# breaking_bitcoin.net
KiCad netlist of a schematic drawn in EAGLE
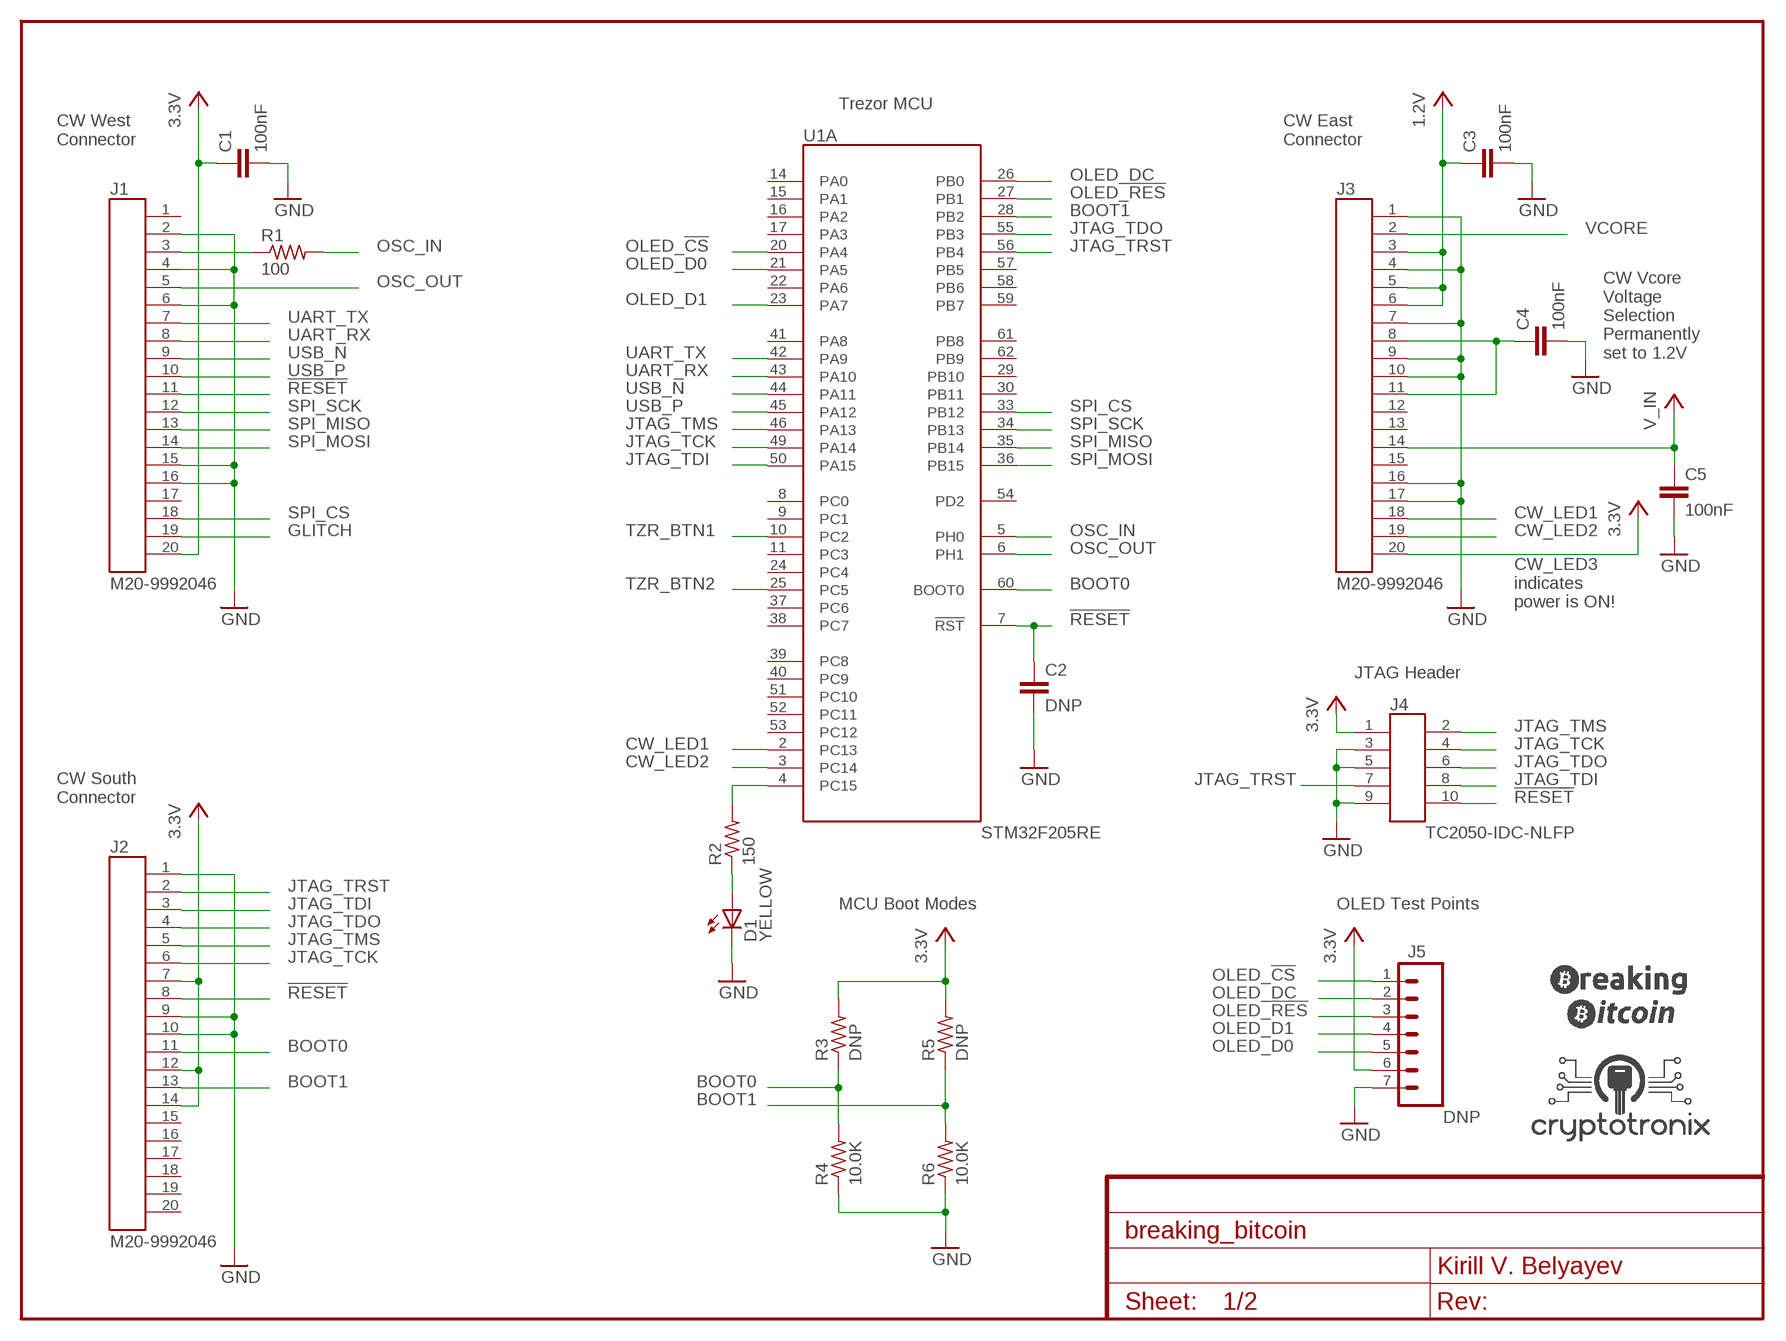
[diagram p0: schematic, sheet 1]
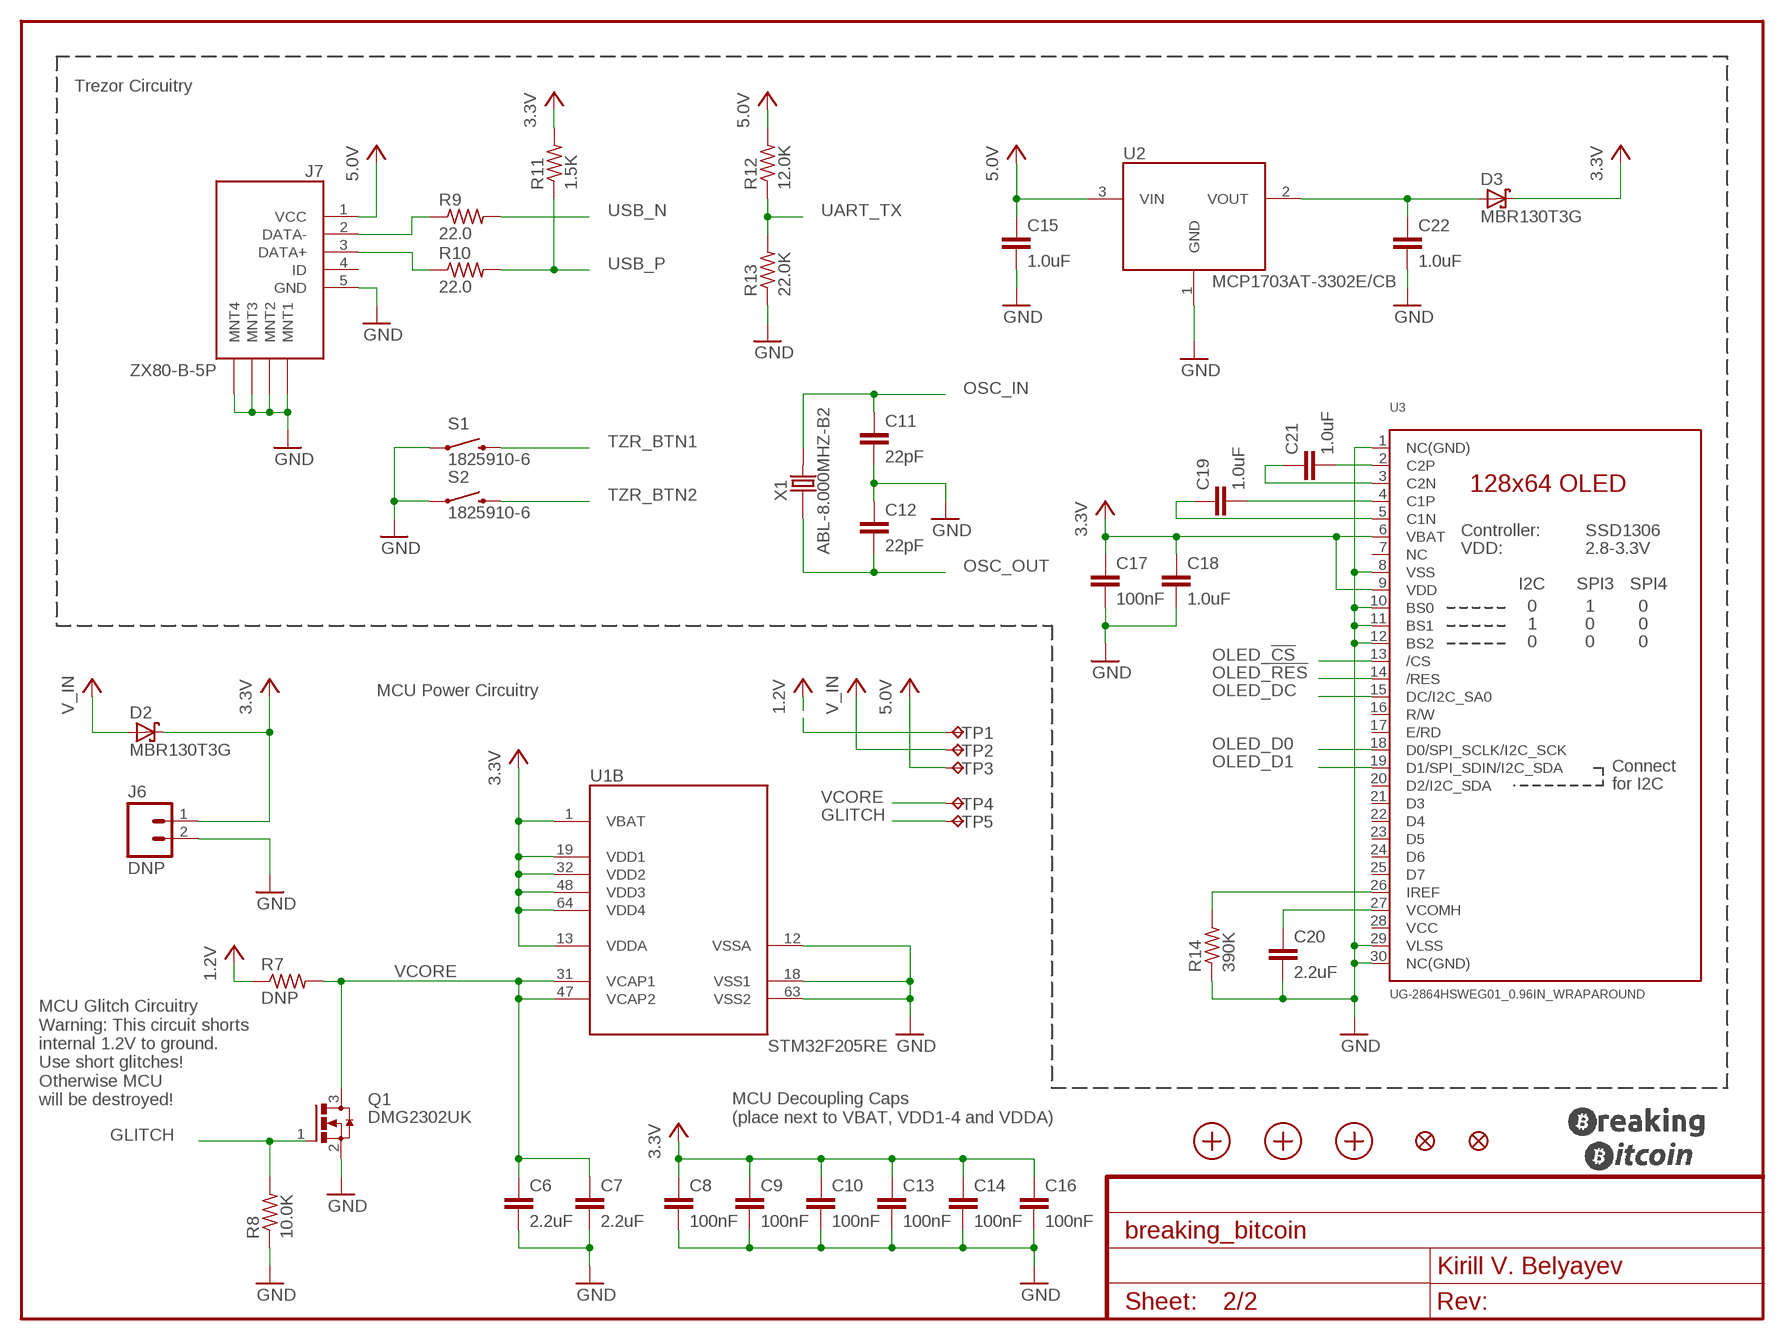
[diagram p1: schematic, sheet 2]

(export (version "E")
  (design (tool "Eeschema 10.0.6"))
  (components
    (comp (ref "C6")
      (value "2.2uF")
      (footprint "eagle-import:C0603")
      (libsource (lib "eagle-import") (part "C-EUC0603"))
    )
    (comp (ref "C7")
      (value "2.2uF")
      (footprint "eagle-import:C0603")
      (libsource (lib "eagle-import") (part "C-EUC0603"))
    )
    (comp (ref "C8")
      (value "100nF")
      (footprint "eagle-import:C0603")
      (libsource (lib "eagle-import") (part "C-EUC0603"))
    )
    (comp (ref "C9")
      (value "100nF")
      (footprint "eagle-import:C0603")
      (libsource (lib "eagle-import") (part "C-EUC0603"))
    )
    (comp (ref "C10")
      (value "100nF")
      (footprint "eagle-import:C0603")
      (libsource (lib "eagle-import") (part "C-EUC0603"))
    )
    (comp (ref "C11")
      (value "22pF")
      (footprint "eagle-import:C0603")
      (libsource (lib "eagle-import") (part "C-EUC0603"))
    )
    (comp (ref "C12")
      (value "22pF")
      (footprint "eagle-import:C0603")
      (libsource (lib "eagle-import") (part "C-EUC0603"))
    )
    (comp (ref "C13")
      (value "100nF")
      (footprint "eagle-import:C0603")
      (libsource (lib "eagle-import") (part "C-EUC0603"))
    )
    (comp (ref "C14")
      (value "100nF")
      (footprint "eagle-import:C0603")
      (libsource (lib "eagle-import") (part "C-EUC0603"))
    )
    (comp (ref "C15")
      (value "1.0uF")
      (footprint "eagle-import:C0603")
      (libsource (lib "eagle-import") (part "C-EUC0603"))
    )
    (comp (ref "C16")
      (value "100nF")
      (footprint "eagle-import:C0603")
      (libsource (lib "eagle-import") (part "C-EUC0603"))
    )
    (comp (ref "C17")
      (value "100nF")
      (footprint "eagle-import:C0603")
      (libsource (lib "eagle-import") (part "C-EUC0603"))
    )
    (comp (ref "C18")
      (value "1.0uF")
      (footprint "eagle-import:C0603")
      (libsource (lib "eagle-import") (part "C-EUC0603"))
    )
    (comp (ref "C19")
      (value "1.0uF")
      (footprint "eagle-import:C0603")
      (libsource (lib "eagle-import") (part "C-EUC0603"))
    )
    (comp (ref "C20")
      (value "2.2uF")
      (footprint "eagle-import:C0603")
      (libsource (lib "eagle-import") (part "C-EUC0603"))
    )
    (comp (ref "C21")
      (value "1.0uF")
      (footprint "eagle-import:C0603")
      (libsource (lib "eagle-import") (part "C-EUC0603"))
    )
    (comp (ref "C22")
      (value "1.0uF")
      (footprint "eagle-import:C0603")
      (libsource (lib "eagle-import") (part "C-EUC0603"))
    )
    (comp (ref "D2")
      (value "MBR130T3G")
      (footprint "eagle-import:SOD123")
      (fields (field (name "MANUFACTURER") "ON Semiconductor"))
      (libsource (lib "eagle-import") (part "MBR130T3G"))
    )
    (comp (ref "D3")
      (value "MBR130T3G")
      (footprint "eagle-import:SOD123")
      (fields (field (name "MANUFACTURER") "ON Semiconductor"))
      (libsource (lib "eagle-import") (part "MBR130T3G"))
    )
    (comp (ref "FD1")
      (value "FIDUCIALUFIDUCIAL")
      (footprint "eagle-import:MICRO-FIDUCIAL")
      (libsource (lib "eagle-import") (part "FIDUCIALUFIDUCIAL"))
    )
    (comp (ref "FD2")
      (value "FIDUCIALUFIDUCIAL")
      (footprint "eagle-import:MICRO-FIDUCIAL")
      (libsource (lib "eagle-import") (part "FIDUCIALUFIDUCIAL"))
    )
    (comp (ref "J6")
      (value "DNP")
      (footprint "eagle-import:M20-9990246")
      (fields (field (name "MAN-PART_NUM") "M20-9990246") (field (name "MANUFACTURER") "Harwin Inc."))
      (libsource (lib "eagle-import") (part "M20-9990246"))
    )
    (comp (ref "J7")
      (value "ZX80-B-5P")
      (footprint "eagle-import:ZX80-B-5P")
      (fields (field (name "MAN-PART_NUM") "ZX80-B-5P(30)") (field (name "MANUFACTURER") "Hirose"))
      (libsource (lib "eagle-import") (part "ZX80-B-5P"))
    )
    (comp (ref "MNT1")
      (value "MOUNT-HOLE-NO-PLATE4-40")
      (footprint "eagle-import:MOUNT-HOLE-NO-PLATE-4-40")
      (libsource (lib "eagle-import") (part "MOUNT-HOLE-NO-PLATE4-40"))
    )
    (comp (ref "MNT2")
      (value "MOUNT-HOLE-NO-PLATE4-40")
      (footprint "eagle-import:MOUNT-HOLE-NO-PLATE-4-40")
      (libsource (lib "eagle-import") (part "MOUNT-HOLE-NO-PLATE4-40"))
    )
    (comp (ref "MNT3")
      (value "MOUNT-HOLE-NO-PLATE4-40")
      (footprint "eagle-import:MOUNT-HOLE-NO-PLATE-4-40")
      (libsource (lib "eagle-import") (part "MOUNT-HOLE-NO-PLATE4-40"))
    )
    (comp (ref "Q1")
      (value "DMG2302UK")
      (footprint "eagle-import:DMG2302UK")
      (fields (field (name "MANUFACTURER") "Diodes Inc."))
      (libsource (lib "eagle-import") (part "DMG2302UK"))
    )
    (comp (ref "R7")
      (value "DNP")
      (footprint "eagle-import:R0603")
      (libsource (lib "eagle-import") (part "R-US_R0603"))
    )
    (comp (ref "R8")
      (value "10.0K")
      (footprint "eagle-import:R0603")
      (libsource (lib "eagle-import") (part "R-US_R0603"))
    )
    (comp (ref "R9")
      (value "22.0")
      (footprint "eagle-import:R0603")
      (libsource (lib "eagle-import") (part "R-US_R0603"))
    )
    (comp (ref "R10")
      (value "22.0")
      (footprint "eagle-import:R0603")
      (libsource (lib "eagle-import") (part "R-US_R0603"))
    )
    (comp (ref "R11")
      (value "1.5K")
      (footprint "eagle-import:R0603")
      (libsource (lib "eagle-import") (part "R-US_R0603"))
    )
    (comp (ref "R12")
      (value "12.0K")
      (footprint "eagle-import:R0603")
      (libsource (lib "eagle-import") (part "R-US_R0603"))
    )
    (comp (ref "R13")
      (value "22.0K")
      (footprint "eagle-import:R0603")
      (libsource (lib "eagle-import") (part "R-US_R0603"))
    )
    (comp (ref "R14")
      (value "390K")
      (footprint "eagle-import:R0603")
      (libsource (lib "eagle-import") (part "R-US_R0603"))
    )
    (comp (ref "S1")
      (value "1825910-6")
      (footprint "eagle-import:SWITCH-TACT-TH")
      (fields
        (field (name "MANUFACTURER") "TE Connectivity")
        (field (name "MAN-PART_NUM") "1825910-6")
        (field (name "MANUFACTURER_1") "TE Connectivity")
      )
      (libsource (lib "eagle-import") (part "SWITCH-TACT-TH"))
    )
    (comp (ref "S2")
      (value "1825910-6")
      (footprint "eagle-import:SWITCH-TACT-TH")
      (fields
        (field (name "MANUFACTURER") "TE Connectivity")
        (field (name "MAN-PART_NUM") "1825910-6")
        (field (name "MANUFACTURER_1") "TE Connectivity")
      )
      (libsource (lib "eagle-import") (part "SWITCH-TACT-TH"))
    )
    (comp (ref "TP1")
      (value "TEST-POINT40MIL")
      (footprint "eagle-import:TEST-POINT-40MILL")
      (libsource (lib "eagle-import") (part "TEST-POINT40MIL"))
    )
    (comp (ref "TP2")
      (value "TEST-POINT40MIL")
      (footprint "eagle-import:TEST-POINT-40MILL")
      (libsource (lib "eagle-import") (part "TEST-POINT40MIL"))
    )
    (comp (ref "TP3")
      (value "TEST-POINT40MIL")
      (footprint "eagle-import:TEST-POINT-40MILL")
      (libsource (lib "eagle-import") (part "TEST-POINT40MIL"))
    )
    (comp (ref "TP4")
      (value "TEST-POINT40MIL")
      (footprint "eagle-import:TEST-POINT-40MILL")
      (libsource (lib "eagle-import") (part "TEST-POINT40MIL"))
    )
    (comp (ref "TP5")
      (value "TEST-POINT40MIL")
      (footprint "eagle-import:TEST-POINT-40MILL")
      (libsource (lib "eagle-import") (part "TEST-POINT40MIL"))
    )
    (comp (ref "U$3")
      (value "BB_LOGO")
      (footprint "eagle-import:BB_LOGO")
      (libsource (lib "eagle-import") (part "BB_LOGO"))
    )
    (comp (ref "U1")
      (value "STM32F205RE")
      (footprint "eagle-import:LQFP64")
      (fields (field (name "MANUFACTURER") "STMicroelectronics"))
      (libsource (lib "eagle-import") (part "STM32F205RE"))
    )
    (comp (ref "U2")
      (value "MCP1703AT-3302E/CB")
      (footprint "eagle-import:MCP1703AT-3302E_CB")
      (fields (field (name "MANUFACTURER") "Microchip Technology"))
      (libsource (lib "eagle-import") (part "MCP1703AT-3302E/CB"))
    )
    (comp (ref "U3")
      (value "UG-2864HSWEG01_0.96IN_WRAPAROUND")
      (footprint "eagle-import:UG-2864HSWEG01_0.96IN_WRAPAROUND")
      (libsource (lib "eagle-import") (part "DISP_OLED_UG-2864HSWEG010.96{dblquote}"))
    )
    (comp (ref "X1")
      (value "ABL-8.000MHZ-B2")
      (footprint "eagle-import:ABL-8.000MHZ-B2")
      (fields (field (name "MANUFACTURER") "Abracon"))
      (libsource (lib "eagle-import") (part "ABL-8.000MHZ-B2"))
    )
    (comp (ref "C1")
      (value "100nF")
      (footprint "eagle-import:C0603")
      (libsource (lib "eagle-import") (part "C-EUC0603"))
    )
    (comp (ref "C2")
      (value "DNP")
      (footprint "eagle-import:C0603")
      (libsource (lib "eagle-import") (part "C-EUC0603"))
    )
    (comp (ref "C3")
      (value "100nF")
      (footprint "eagle-import:C0603")
      (libsource (lib "eagle-import") (part "C-EUC0603"))
    )
    (comp (ref "C4")
      (value "100nF")
      (footprint "eagle-import:C0603")
      (libsource (lib "eagle-import") (part "C-EUC0603"))
    )
    (comp (ref "C5")
      (value "100nF")
      (footprint "eagle-import:C0603")
      (libsource (lib "eagle-import") (part "C-EUC0603"))
    )
    (comp (ref "D1")
      (value "YELLOW")
      (footprint "eagle-import:0603")
      (fields (field (name "MAN-PART_NUM") "LTST-C190") (field (name "MANUFACTURER") "Lite-On Inc."))
      (libsource (lib "eagle-import") (part "LTST-C190YKT"))
    )
    (comp (ref "J1")
      (value "M20-9992046")
      (footprint "eagle-import:M20-9992046")
      (fields (field (name "MANUFACTURER") "Harwin Inc."))
      (libsource (lib "eagle-import") (part "M20-9992046"))
    )
    (comp (ref "J2")
      (value "M20-9992046")
      (footprint "eagle-import:M20-9992046")
      (fields (field (name "MANUFACTURER") "Harwin Inc."))
      (libsource (lib "eagle-import") (part "M20-9992046"))
    )
    (comp (ref "J3")
      (value "M20-9992046")
      (footprint "eagle-import:M20-9992046")
      (fields (field (name "MANUFACTURER") "Harwin Inc."))
      (libsource (lib "eagle-import") (part "M20-9992046"))
    )
    (comp (ref "J4")
      (value "TC2050-IDC-NLFP")
      (footprint "eagle-import:TC2050-IDC-NLFP")
      (fields (field (name "MANUFACTURER") "Tag Connect"))
      (libsource (lib "eagle-import") (part "TC2050-IDC-NLFP"))
    )
    (comp (ref "J5")
      (value "DNP")
      (footprint "eagle-import:1X07")
      (libsource (lib "eagle-import") (part "M07"))
    )
    (comp (ref "R1")
      (value "100")
      (footprint "eagle-import:R0603")
      (libsource (lib "eagle-import") (part "R-US_R0603"))
    )
    (comp (ref "R2")
      (value "150")
      (footprint "eagle-import:R0603")
      (libsource (lib "eagle-import") (part "R-US_R0603"))
    )
    (comp (ref "R3")
      (value "DNP")
      (footprint "eagle-import:R0603")
      (libsource (lib "eagle-import") (part "R-US_R0603"))
    )
    (comp (ref "R4")
      (value "10.0K")
      (footprint "eagle-import:R0603")
      (libsource (lib "eagle-import") (part "R-US_R0603"))
    )
    (comp (ref "R5")
      (value "DNP")
      (footprint "eagle-import:R0603")
      (libsource (lib "eagle-import") (part "R-US_R0603"))
    )
    (comp (ref "R6")
      (value "10.0K")
      (footprint "eagle-import:R0603")
      (libsource (lib "eagle-import") (part "R-US_R0603"))
    )
    (comp (ref "U$1")
      (value "BB_LOGO")
      (footprint "eagle-import:BB_LOGO")
      (libsource (lib "eagle-import") (part "BB_LOGO"))
    )
    (comp (ref "U$2")
      (value "CRYPTOTRONIX_LOGO")
      (footprint "eagle-import:CRYPTOTRONIX_LOGO")
      (libsource (lib "eagle-import") (part "CRYPTOTRONIX_LOGO"))
    )
  )
  (nets
    (net (code "1") (name "0V") (class "Default")
      (node (ref "C1") (pin "2") (pinfunction "2_2") (pintype "passive"))
      (node (ref "C10") (pin "2") (pinfunction "2_2") (pintype "passive"))
      (node (ref "C11") (pin "2") (pinfunction "2_2") (pintype "passive"))
      (node (ref "C12") (pin "1") (pinfunction "1_1") (pintype "passive"))
      (node (ref "C13") (pin "2") (pinfunction "2_2") (pintype "passive"))
      (node (ref "C14") (pin "2") (pinfunction "2_2") (pintype "passive"))
      (node (ref "C15") (pin "2") (pinfunction "2_2") (pintype "passive"))
      (node (ref "C16") (pin "2") (pinfunction "2_2") (pintype "passive"))
      (node (ref "C17") (pin "2") (pinfunction "2_2") (pintype "passive"))
      (node (ref "C18") (pin "2") (pinfunction "2_2") (pintype "passive"))
      (node (ref "C2") (pin "2") (pinfunction "2_2") (pintype "passive"))
      (node (ref "C20") (pin "2") (pinfunction "2_2") (pintype "passive"))
      (node (ref "C22") (pin "2") (pinfunction "2_2") (pintype "passive"))
      (node (ref "C3") (pin "2") (pinfunction "2_2") (pintype "passive"))
      (node (ref "C4") (pin "2") (pinfunction "2_2") (pintype "passive"))
      (node (ref "C5") (pin "2") (pinfunction "2_2") (pintype "passive"))
      (node (ref "C6") (pin "2") (pinfunction "2_2") (pintype "passive"))
      (node (ref "C7") (pin "2") (pinfunction "2_2") (pintype "passive"))
      (node (ref "C8") (pin "2") (pinfunction "2_2") (pintype "passive"))
      (node (ref "C9") (pin "2") (pinfunction "2_2") (pintype "passive"))
      (node (ref "D1") (pin "C") (pinfunction "C_C") (pintype "passive"))
      (node (ref "J1") (pin "15") (pinfunction "P$15_15") (pintype "bidirectional"))
      (node (ref "J1") (pin "16") (pinfunction "P$16_16") (pintype "bidirectional"))
      (node (ref "J1") (pin "2") (pinfunction "P$2_2") (pintype "bidirectional"))
      (node (ref "J1") (pin "4") (pinfunction "P$4_4") (pintype "bidirectional"))
      (node (ref "J1") (pin "6") (pinfunction "P$6_6") (pintype "bidirectional"))
      (node (ref "J2") (pin "1") (pinfunction "P$1_1") (pintype "bidirectional"))
      (node (ref "J2") (pin "10") (pinfunction "P$10_10") (pintype "bidirectional"))
      (node (ref "J2") (pin "9") (pinfunction "P$9_9") (pintype "bidirectional"))
      (node (ref "J3") (pin "1") (pinfunction "P$1_1") (pintype "bidirectional"))
      (node (ref "J3") (pin "10") (pinfunction "P$10_10") (pintype "bidirectional"))
      (node (ref "J3") (pin "16") (pinfunction "P$16_16") (pintype "bidirectional"))
      (node (ref "J3") (pin "17") (pinfunction "P$17_17") (pintype "bidirectional"))
      (node (ref "J3") (pin "4") (pinfunction "P$4_4") (pintype "bidirectional"))
      (node (ref "J3") (pin "7") (pinfunction "P$7_7") (pintype "bidirectional"))
      (node (ref "J3") (pin "9") (pinfunction "P$9_9") (pintype "bidirectional"))
      (node (ref "J4") (pin "3") (pinfunction "P$3_3") (pintype "bidirectional"))
      (node (ref "J4") (pin "5") (pinfunction "P$5_5") (pintype "bidirectional"))
      (node (ref "J4") (pin "9") (pinfunction "P$9_9") (pintype "bidirectional"))
      (node (ref "J5") (pin "7") (pinfunction "7_7") (pintype "passive"))
      (node (ref "J6") (pin "2") (pinfunction "2_2") (pintype "passive"))
      (node (ref "J7") (pin "5") (pinfunction "GND_5") (pintype "bidirectional"))
      (node (ref "J7") (pin "M1") (pinfunction "MNT1_M1") (pintype "bidirectional"))
      (node (ref "J7") (pin "M2") (pinfunction "MNT2_M2") (pintype "bidirectional"))
      (node (ref "J7") (pin "M3") (pinfunction "MNT3_M3") (pintype "bidirectional"))
      (node (ref "J7") (pin "M4") (pinfunction "MNT4_M4") (pintype "bidirectional"))
      (node (ref "Q1") (pin "2") (pinfunction "S_2") (pintype "passive"))
      (node (ref "R13") (pin "1") (pinfunction "1_1") (pintype "passive"))
      (node (ref "R14") (pin "1") (pinfunction "1_1") (pintype "passive"))
      (node (ref "R4") (pin "1") (pinfunction "1_1") (pintype "passive"))
      (node (ref "R6") (pin "1") (pinfunction "1_1") (pintype "passive"))
      (node (ref "R8") (pin "1") (pinfunction "1_1") (pintype "passive"))
      (node (ref "S1") (pin "1") (pinfunction "1_1") (pintype "passive"))
      (node (ref "S2") (pin "1") (pinfunction "1_1") (pintype "passive"))
      (node (ref "U1") (pin "12") (pinfunction "VSSA_12") (pintype "bidirectional"))
      (node (ref "U1") (pin "18") (pinfunction "VSS1_18") (pintype "bidirectional"))
      (node (ref "U1") (pin "63") (pinfunction "VSS2_63") (pintype "bidirectional"))
      (node (ref "U2") (pin "1") (pinfunction "GND_1") (pintype "bidirectional"))
      (node (ref "U3") (pin "1") (pinfunction "NC(GND)_1") (pintype "input"))
      (node (ref "U3") (pin "10") (pinfunction "BS0_10") (pintype "input"))
      (node (ref "U3") (pin "11") (pinfunction "BS1_11") (pintype "input"))
      (node (ref "U3") (pin "12") (pinfunction "BS2_12") (pintype "input"))
      (node (ref "U3") (pin "29") (pinfunction "VLSS_29") (pintype "power_in"))
      (node (ref "U3") (pin "30") (pinfunction "NC(GND)_30") (pintype "input"))
      (node (ref "U3") (pin "8") (pinfunction "VSS_8") (pintype "power_in"))
    )
    (net (code "2") (name "1.2V") (class "Default")
      (node (ref "C3") (pin "1") (pinfunction "1_1") (pintype "passive"))
      (node (ref "J3") (pin "3") (pinfunction "P$3_3") (pintype "bidirectional"))
      (node (ref "J3") (pin "5") (pinfunction "P$5_5") (pintype "bidirectional"))
      (node (ref "J3") (pin "6") (pinfunction "P$6_6") (pintype "bidirectional"))
      (node (ref "R7") (pin "1") (pinfunction "1_1") (pintype "passive"))
      (node (ref "TP1") (pin "1") (pinfunction "PP_1") (pintype "input"))
    )
    (net (code "3") (name "3.3V") (class "Default")
      (node (ref "C1") (pin "1") (pinfunction "1_1") (pintype "passive"))
      (node (ref "C10") (pin "1") (pinfunction "1_1") (pintype "passive"))
      (node (ref "C13") (pin "1") (pinfunction "1_1") (pintype "passive"))
      (node (ref "C14") (pin "1") (pinfunction "1_1") (pintype "passive"))
      (node (ref "C16") (pin "1") (pinfunction "1_1") (pintype "passive"))
      (node (ref "C17") (pin "1") (pinfunction "1_1") (pintype "passive"))
      (node (ref "C18") (pin "1") (pinfunction "1_1") (pintype "passive"))
      (node (ref "C8") (pin "1") (pinfunction "1_1") (pintype "passive"))
      (node (ref "C9") (pin "1") (pinfunction "1_1") (pintype "passive"))
      (node (ref "D2") (pin "C") (pinfunction "C_C") (pintype "passive"))
      (node (ref "D3") (pin "C") (pinfunction "C_C") (pintype "passive"))
      (node (ref "J1") (pin "20") (pinfunction "P$20_20") (pintype "bidirectional"))
      (node (ref "J2") (pin "12") (pinfunction "P$12_12") (pintype "bidirectional"))
      (node (ref "J2") (pin "14") (pinfunction "P$14_14") (pintype "bidirectional"))
      (node (ref "J2") (pin "7") (pinfunction "P$7_7") (pintype "bidirectional"))
      (node (ref "J3") (pin "20") (pinfunction "P$20_20") (pintype "bidirectional"))
      (node (ref "J4") (pin "1") (pinfunction "P$1_1") (pintype "bidirectional"))
      (node (ref "J5") (pin "6") (pinfunction "6_6") (pintype "passive"))
      (node (ref "J6") (pin "1") (pinfunction "1_1") (pintype "passive"))
      (node (ref "R11") (pin "2") (pinfunction "2_2") (pintype "passive"))
      (node (ref "R3") (pin "2") (pinfunction "2_2") (pintype "passive"))
      (node (ref "R5") (pin "2") (pinfunction "2_2") (pintype "passive"))
      (node (ref "U1") (pin "1") (pinfunction "VBAT_1") (pintype "bidirectional"))
      (node (ref "U1") (pin "13") (pinfunction "VDDA_13") (pintype "bidirectional"))
      (node (ref "U1") (pin "19") (pinfunction "VDD1_19") (pintype "bidirectional"))
      (node (ref "U1") (pin "32") (pinfunction "VDD2_32") (pintype "bidirectional"))
      (node (ref "U1") (pin "48") (pinfunction "VDD3_48") (pintype "bidirectional"))
      (node (ref "U1") (pin "64") (pinfunction "VDD4_64") (pintype "bidirectional"))
      (node (ref "U3") (pin "6") (pinfunction "VBAT_6") (pintype "input"))
      (node (ref "U3") (pin "9") (pinfunction "VDD_9") (pintype "power_in"))
    )
    (net (code "4") (name "5.0V") (class "Default")
      (node (ref "C15") (pin "1") (pinfunction "1_1") (pintype "passive"))
      (node (ref "J7") (pin "1") (pinfunction "VCC_1") (pintype "bidirectional"))
      (node (ref "R12") (pin "2") (pinfunction "2_2") (pintype "passive"))
      (node (ref "TP3") (pin "1") (pinfunction "PP_1") (pintype "input"))
      (node (ref "U2") (pin "3") (pinfunction "VIN_3") (pintype "bidirectional"))
    )
    (net (code "5") (name "BOOT0") (class "Default")
      (node (ref "J2") (pin "11") (pinfunction "P$11_11") (pintype "bidirectional"))
      (node (ref "R3") (pin "1") (pinfunction "1_1") (pintype "passive"))
      (node (ref "R4") (pin "2") (pinfunction "2_2") (pintype "passive"))
      (node (ref "U1") (pin "60") (pinfunction "BOOT0_60") (pintype "bidirectional"))
    )
    (net (code "6") (name "BOOT1") (class "Default")
      (node (ref "J2") (pin "13") (pinfunction "P$13_13") (pintype "bidirectional"))
      (node (ref "R5") (pin "1") (pinfunction "1_1") (pintype "passive"))
      (node (ref "R6") (pin "2") (pinfunction "2_2") (pintype "passive"))
      (node (ref "U1") (pin "28") (pinfunction "PB2_28") (pintype "bidirectional"))
    )
    (net (code "7") (name "CW_LED1") (class "Default")
      (node (ref "J3") (pin "18") (pinfunction "P$18_18") (pintype "bidirectional"))
      (node (ref "U1") (pin "2") (pinfunction "PC13_2") (pintype "bidirectional"))
    )
    (net (code "8") (name "CW_LED2") (class "Default")
      (node (ref "J3") (pin "19") (pinfunction "P$19_19") (pintype "bidirectional"))
      (node (ref "U1") (pin "3") (pinfunction "PC14_3") (pintype "bidirectional"))
    )
    (net (code "9") (name "GLITCH") (class "Default")
      (node (ref "J1") (pin "19") (pinfunction "P$19_19") (pintype "bidirectional"))
      (node (ref "Q1") (pin "1") (pinfunction "G_1") (pintype "passive"))
      (node (ref "R8") (pin "2") (pinfunction "2_2") (pintype "passive"))
      (node (ref "TP5") (pin "1") (pinfunction "PP_1") (pintype "input"))
    )
    (net (code "10") (name "JTAG_TCK") (class "Default")
      (node (ref "J2") (pin "6") (pinfunction "P$6_6") (pintype "bidirectional"))
      (node (ref "J4") (pin "4") (pinfunction "P$4_4") (pintype "bidirectional"))
      (node (ref "U1") (pin "49") (pinfunction "PA14_49") (pintype "bidirectional"))
    )
    (net (code "11") (name "JTAG_TDI") (class "Default")
      (node (ref "J2") (pin "3") (pinfunction "P$3_3") (pintype "bidirectional"))
      (node (ref "J4") (pin "8") (pinfunction "P$8_8") (pintype "bidirectional"))
      (node (ref "U1") (pin "50") (pinfunction "PA15_50") (pintype "bidirectional"))
    )
    (net (code "12") (name "JTAG_TDO") (class "Default")
      (node (ref "J2") (pin "4") (pinfunction "P$4_4") (pintype "bidirectional"))
      (node (ref "J4") (pin "6") (pinfunction "P$6_6") (pintype "bidirectional"))
      (node (ref "U1") (pin "55") (pinfunction "PB3_55") (pintype "bidirectional"))
    )
    (net (code "13") (name "JTAG_TMS") (class "Default")
      (node (ref "J2") (pin "5") (pinfunction "P$5_5") (pintype "bidirectional"))
      (node (ref "J4") (pin "2") (pinfunction "P$2_2") (pintype "bidirectional"))
      (node (ref "U1") (pin "46") (pinfunction "PA13_46") (pintype "bidirectional"))
    )
    (net (code "14") (name "JTAG_TRST") (class "Default")
      (node (ref "J2") (pin "2") (pinfunction "P$2_2") (pintype "bidirectional"))
      (node (ref "J4") (pin "7") (pinfunction "P$7_7") (pintype "bidirectional"))
      (node (ref "U1") (pin "56") (pinfunction "PB4_56") (pintype "bidirectional"))
    )
    (net (code "15") (name "Net-(D1-PadA)") (class "Default")
      (node (ref "D1") (pin "A") (pinfunction "A_A") (pintype "passive"))
      (node (ref "R2") (pin "1") (pinfunction "1_1") (pintype "passive"))
    )
    (net (code "16") (name "Net-(J1-P$3)") (class "Default")
      (node (ref "J1") (pin "3") (pinfunction "P$3_3") (pintype "bidirectional"))
      (node (ref "R1") (pin "1") (pinfunction "1_1") (pintype "passive"))
    )
    (net (code "17") (name "Net-(J3-P$11)") (class "Default")
      (node (ref "C4") (pin "1") (pinfunction "1_1") (pintype "passive"))
      (node (ref "J3") (pin "11") (pinfunction "P$11_11") (pintype "bidirectional"))
      (node (ref "J3") (pin "8") (pinfunction "P$8_8") (pintype "bidirectional"))
    )
    (net (code "18") (name "Net-(J7-DATA+)") (class "Default")
      (node (ref "J7") (pin "3") (pinfunction "DATA+_3") (pintype "bidirectional"))
      (node (ref "R10") (pin "1") (pinfunction "1_1") (pintype "passive"))
    )
    (net (code "19") (name "Net-(J7-DATA-)") (class "Default")
      (node (ref "J7") (pin "2") (pinfunction "DATA-_2") (pintype "bidirectional"))
      (node (ref "R9") (pin "1") (pinfunction "1_1") (pintype "passive"))
    )
    (net (code "20") (name "Net-(U1A-PC15)") (class "Default")
      (node (ref "R2") (pin "2") (pinfunction "2_2") (pintype "passive"))
      (node (ref "U1") (pin "4") (pinfunction "PC15_4") (pintype "bidirectional"))
    )
    (net (code "21") (name "Net-(U2-VOUT)") (class "Default")
      (node (ref "C22") (pin "1") (pinfunction "1_1") (pintype "passive"))
      (node (ref "D3") (pin "A") (pinfunction "A_A") (pintype "passive"))
      (node (ref "U2") (pin "2") (pinfunction "VOUT_2") (pintype "bidirectional"))
    )
    (net (code "22") (name "Net-(U3-C1N)") (class "Default")
      (node (ref "C19") (pin "1") (pinfunction "1_1") (pintype "passive"))
      (node (ref "U3") (pin "5") (pinfunction "C1N_5") (pintype "input"))
    )
    (net (code "23") (name "Net-(U3-C1P)") (class "Default")
      (node (ref "C19") (pin "2") (pinfunction "2_2") (pintype "passive"))
      (node (ref "U3") (pin "4") (pinfunction "C1P_4") (pintype "input"))
    )
    (net (code "24") (name "Net-(U3-C2N)") (class "Default")
      (node (ref "C21") (pin "1") (pinfunction "1_1") (pintype "passive"))
      (node (ref "U3") (pin "3") (pinfunction "C2N_3") (pintype "input"))
    )
    (net (code "25") (name "Net-(U3-C2P)") (class "Default")
      (node (ref "C21") (pin "2") (pinfunction "2_2") (pintype "passive"))
      (node (ref "U3") (pin "2") (pinfunction "C2P_2") (pintype "input"))
    )
    (net (code "26") (name "Net-(U3-IREF)") (class "Default")
      (node (ref "R14") (pin "2") (pinfunction "2_2") (pintype "passive"))
      (node (ref "U3") (pin "26") (pinfunction "IREF_26") (pintype "input"))
    )
    (net (code "27") (name "Net-(U3-VCOMH)") (class "Default")
      (node (ref "C20") (pin "1") (pinfunction "1_1") (pintype "passive"))
      (node (ref "U3") (pin "27") (pinfunction "VCOMH_27") (pintype "output"))
    )
    (net (code "28") (name "OLED_D0") (class "Default")
      (node (ref "J5") (pin "5") (pinfunction "5_5") (pintype "passive"))
      (node (ref "U1") (pin "21") (pinfunction "PA5_21") (pintype "bidirectional"))
      (node (ref "U3") (pin "18") (pinfunction "D0/SPI_SCLK/I2C_SCK_18") (pintype "bidirectional"))
    )
    (net (code "29") (name "OLED_D1") (class "Default")
      (node (ref "J5") (pin "4") (pinfunction "4_4") (pintype "passive"))
      (node (ref "U1") (pin "23") (pinfunction "PA7_23") (pintype "bidirectional"))
      (node (ref "U3") (pin "19") (pinfunction "D1/SPI_SDIN/I2C_SDA_19") (pintype "bidirectional"))
    )
    (net (code "30") (name "OLED_DC") (class "Default")
      (node (ref "J5") (pin "2") (pinfunction "2_2") (pintype "passive"))
      (node (ref "U1") (pin "26") (pinfunction "PB0_26") (pintype "bidirectional"))
      (node (ref "U3") (pin "15") (pinfunction "DC/I2C_SA0_15") (pintype "input"))
    )
    (net (code "31") (name "OLED_~{CS}") (class "Default")
      (node (ref "J5") (pin "1") (pinfunction "1_1") (pintype "passive"))
      (node (ref "U1") (pin "20") (pinfunction "PA4_20") (pintype "bidirectional"))
      (node (ref "U3") (pin "13") (pinfunction "/CS_13") (pintype "input"))
    )
    (net (code "32") (name "OLED_~{RES}") (class "Default")
      (node (ref "J5") (pin "3") (pinfunction "3_3") (pintype "passive"))
      (node (ref "U1") (pin "27") (pinfunction "PB1_27") (pintype "bidirectional"))
      (node (ref "U3") (pin "14") (pinfunction "/RES_14") (pintype "input"))
    )
    (net (code "33") (name "OSC_IN") (class "Default")
      (node (ref "C11") (pin "1") (pinfunction "1_1") (pintype "passive"))
      (node (ref "R1") (pin "2") (pinfunction "2_2") (pintype "passive"))
      (node (ref "U1") (pin "5") (pinfunction "PH0_5") (pintype "bidirectional"))
      (node (ref "X1") (pin "2") (pinfunction "2_2") (pintype "passive"))
    )
    (net (code "34") (name "OSC_OUT") (class "Default")
      (node (ref "C12") (pin "2") (pinfunction "2_2") (pintype "passive"))
      (node (ref "J1") (pin "5") (pinfunction "P$5_5") (pintype "bidirectional"))
      (node (ref "U1") (pin "6") (pinfunction "PH1_6") (pintype "bidirectional"))
      (node (ref "X1") (pin "1") (pinfunction "1_1") (pintype "passive"))
    )
    (net (code "35") (name "SPI_CS") (class "Default")
      (node (ref "J1") (pin "18") (pinfunction "P$18_18") (pintype "bidirectional"))
      (node (ref "U1") (pin "33") (pinfunction "PB12_33") (pintype "bidirectional"))
    )
    (net (code "36") (name "SPI_MISO") (class "Default")
      (node (ref "J1") (pin "13") (pinfunction "P$13_13") (pintype "bidirectional"))
      (node (ref "U1") (pin "35") (pinfunction "PB14_35") (pintype "bidirectional"))
    )
    (net (code "37") (name "SPI_MOSI") (class "Default")
      (node (ref "J1") (pin "14") (pinfunction "P$14_14") (pintype "bidirectional"))
      (node (ref "U1") (pin "36") (pinfunction "PB15_36") (pintype "bidirectional"))
    )
    (net (code "38") (name "SPI_SCK") (class "Default")
      (node (ref "J1") (pin "12") (pinfunction "P$12_12") (pintype "bidirectional"))
      (node (ref "U1") (pin "34") (pinfunction "PB13_34") (pintype "bidirectional"))
    )
    (net (code "39") (name "TZR_BTN1") (class "Default")
      (node (ref "S1") (pin "3") (pinfunction "2_3") (pintype "passive"))
      (node (ref "U1") (pin "10") (pinfunction "PC2_10") (pintype "bidirectional"))
    )
    (net (code "40") (name "TZR_BTN2") (class "Default")
      (node (ref "S2") (pin "3") (pinfunction "2_3") (pintype "passive"))
      (node (ref "U1") (pin "25") (pinfunction "PC5_25") (pintype "bidirectional"))
    )
    (net (code "41") (name "UART_RX") (class "Default")
      (node (ref "J1") (pin "8") (pinfunction "P$8_8") (pintype "bidirectional"))
      (node (ref "U1") (pin "43") (pinfunction "PA10_43") (pintype "bidirectional"))
    )
    (net (code "42") (name "UART_TX") (class "Default")
      (node (ref "J1") (pin "7") (pinfunction "P$7_7") (pintype "bidirectional"))
      (node (ref "R12") (pin "1") (pinfunction "1_1") (pintype "passive"))
      (node (ref "R13") (pin "2") (pinfunction "2_2") (pintype "passive"))
      (node (ref "U1") (pin "42") (pinfunction "PA9_42") (pintype "bidirectional"))
    )
    (net (code "43") (name "USB_N") (class "Default")
      (node (ref "J1") (pin "9") (pinfunction "P$9_9") (pintype "bidirectional"))
      (node (ref "R9") (pin "2") (pinfunction "2_2") (pintype "passive"))
      (node (ref "U1") (pin "44") (pinfunction "PA11_44") (pintype "bidirectional"))
    )
    (net (code "44") (name "USB_P") (class "Default")
      (node (ref "J1") (pin "10") (pinfunction "P$10_10") (pintype "bidirectional"))
      (node (ref "R10") (pin "2") (pinfunction "2_2") (pintype "passive"))
      (node (ref "R11") (pin "1") (pinfunction "1_1") (pintype "passive"))
      (node (ref "U1") (pin "45") (pinfunction "PA12_45") (pintype "bidirectional"))
    )
    (net (code "45") (name "VCC") (class "Default")
      (node (ref "U3") (pin "28") (pinfunction "VCC_28") (pintype "power_in"))
    )
    (net (code "46") (name "VCORE") (class "Default")
      (node (ref "C6") (pin "1") (pinfunction "1_1") (pintype "passive"))
      (node (ref "C7") (pin "1") (pinfunction "1_1") (pintype "passive"))
      (node (ref "J3") (pin "2") (pinfunction "P$2_2") (pintype "bidirectional"))
      (node (ref "Q1") (pin "3") (pinfunction "D_3") (pintype "passive"))
      (node (ref "R7") (pin "2") (pinfunction "2_2") (pintype "passive"))
      (node (ref "TP4") (pin "1") (pinfunction "PP_1") (pintype "input"))
      (node (ref "U1") (pin "31") (pinfunction "VCAP1_31") (pintype "bidirectional"))
      (node (ref "U1") (pin "47") (pinfunction "VCAP2_47") (pintype "bidirectional"))
    )
    (net (code "47") (name "V_IN") (class "Default")
      (node (ref "C5") (pin "1") (pinfunction "1_1") (pintype "passive"))
      (node (ref "D2") (pin "A") (pinfunction "A_A") (pintype "passive"))
      (node (ref "J3") (pin "14") (pinfunction "P$14_14") (pintype "bidirectional"))
      (node (ref "TP2") (pin "1") (pinfunction "PP_1") (pintype "input"))
    )
    (net (code "48") (name "unconnected-(J1-P$1-Pad1)") (class "Default")
      (node (ref "J1") (pin "1") (pinfunction "P$1_1") (pintype "bidirectional"))
    )
    (net (code "49") (name "unconnected-(J1-P$17-Pad17)") (class "Default")
      (node (ref "J1") (pin "17") (pinfunction "P$17_17") (pintype "bidirectional"))
    )
    (net (code "50") (name "unconnected-(J2-P$15-Pad15)") (class "Default")
      (node (ref "J2") (pin "15") (pinfunction "P$15_15") (pintype "bidirectional"))
    )
    (net (code "51") (name "unconnected-(J2-P$16-Pad16)") (class "Default")
      (node (ref "J2") (pin "16") (pinfunction "P$16_16") (pintype "bidirectional"))
    )
    (net (code "52") (name "unconnected-(J2-P$17-Pad17)") (class "Default")
      (node (ref "J2") (pin "17") (pinfunction "P$17_17") (pintype "bidirectional"))
    )
    (net (code "53") (name "unconnected-(J2-P$18-Pad18)") (class "Default")
      (node (ref "J2") (pin "18") (pinfunction "P$18_18") (pintype "bidirectional"))
    )
    (net (code "54") (name "unconnected-(J2-P$19-Pad19)") (class "Default")
      (node (ref "J2") (pin "19") (pinfunction "P$19_19") (pintype "bidirectional"))
    )
    (net (code "55") (name "unconnected-(J2-P$20-Pad20)") (class "Default")
      (node (ref "J2") (pin "20") (pinfunction "P$20_20") (pintype "bidirectional"))
    )
    (net (code "56") (name "unconnected-(J3-P$12-Pad12)") (class "Default")
      (node (ref "J3") (pin "12") (pinfunction "P$12_12") (pintype "bidirectional"))
    )
    (net (code "57") (name "unconnected-(J3-P$13-Pad13)") (class "Default")
      (node (ref "J3") (pin "13") (pinfunction "P$13_13") (pintype "bidirectional"))
    )
    (net (code "58") (name "unconnected-(J3-P$15-Pad15)") (class "Default")
      (node (ref "J3") (pin "15") (pinfunction "P$15_15") (pintype "bidirectional"))
    )
    (net (code "59") (name "unconnected-(J7-ID-Pad4)") (class "Default")
      (node (ref "J7") (pin "4") (pinfunction "ID_4") (pintype "bidirectional"))
    )
    (net (code "60") (name "unconnected-(U1A-PA0-Pad14)") (class "Default")
      (node (ref "U1") (pin "14") (pinfunction "PA0_14") (pintype "bidirectional"))
    )
    (net (code "61") (name "unconnected-(U1A-PA1-Pad15)") (class "Default")
      (node (ref "U1") (pin "15") (pinfunction "PA1_15") (pintype "bidirectional"))
    )
    (net (code "62") (name "unconnected-(U1A-PA2-Pad16)") (class "Default")
      (node (ref "U1") (pin "16") (pinfunction "PA2_16") (pintype "bidirectional"))
    )
    (net (code "63") (name "unconnected-(U1A-PA3-Pad17)") (class "Default")
      (node (ref "U1") (pin "17") (pinfunction "PA3_17") (pintype "bidirectional"))
    )
    (net (code "64") (name "unconnected-(U1A-PA6-Pad22)") (class "Default")
      (node (ref "U1") (pin "22") (pinfunction "PA6_22") (pintype "bidirectional"))
    )
    (net (code "65") (name "unconnected-(U1A-PA8-Pad41)") (class "Default")
      (node (ref "U1") (pin "41") (pinfunction "PA8_41") (pintype "bidirectional"))
    )
    (net (code "66") (name "unconnected-(U1A-PB5-Pad57)") (class "Default")
      (node (ref "U1") (pin "57") (pinfunction "PB5_57") (pintype "bidirectional"))
    )
    (net (code "67") (name "unconnected-(U1A-PB6-Pad58)") (class "Default")
      (node (ref "U1") (pin "58") (pinfunction "PB6_58") (pintype "bidirectional"))
    )
    (net (code "68") (name "unconnected-(U1A-PB7-Pad59)") (class "Default")
      (node (ref "U1") (pin "59") (pinfunction "PB7_59") (pintype "bidirectional"))
    )
    (net (code "69") (name "unconnected-(U1A-PB8-Pad61)") (class "Default")
      (node (ref "U1") (pin "61") (pinfunction "PB8_61") (pintype "bidirectional"))
    )
    (net (code "70") (name "unconnected-(U1A-PB9-Pad62)") (class "Default")
      (node (ref "U1") (pin "62") (pinfunction "PB9_62") (pintype "bidirectional"))
    )
    (net (code "71") (name "unconnected-(U1A-PB10-Pad29)") (class "Default")
      (node (ref "U1") (pin "29") (pinfunction "PB10_29") (pintype "bidirectional"))
    )
    (net (code "72") (name "unconnected-(U1A-PB11-Pad30)") (class "Default")
      (node (ref "U1") (pin "30") (pinfunction "PB11_30") (pintype "bidirectional"))
    )
    (net (code "73") (name "unconnected-(U1A-PC0-Pad8)") (class "Default")
      (node (ref "U1") (pin "8") (pinfunction "PC0_8") (pintype "bidirectional"))
    )
    (net (code "74") (name "unconnected-(U1A-PC1-Pad9)") (class "Default")
      (node (ref "U1") (pin "9") (pinfunction "PC1_9") (pintype "bidirectional"))
    )
    (net (code "75") (name "unconnected-(U1A-PC3-Pad11)") (class "Default")
      (node (ref "U1") (pin "11") (pinfunction "PC3_11") (pintype "bidirectional"))
    )
    (net (code "76") (name "unconnected-(U1A-PC4-Pad24)") (class "Default")
      (node (ref "U1") (pin "24") (pinfunction "PC4_24") (pintype "bidirectional"))
    )
    (net (code "77") (name "unconnected-(U1A-PC6-Pad37)") (class "Default")
      (node (ref "U1") (pin "37") (pinfunction "PC6_37") (pintype "bidirectional"))
    )
    (net (code "78") (name "unconnected-(U1A-PC7-Pad38)") (class "Default")
      (node (ref "U1") (pin "38") (pinfunction "PC7_38") (pintype "bidirectional"))
    )
    (net (code "79") (name "unconnected-(U1A-PC8-Pad39)") (class "Default")
      (node (ref "U1") (pin "39") (pinfunction "PC8_39") (pintype "bidirectional"))
    )
    (net (code "80") (name "unconnected-(U1A-PC9-Pad40)") (class "Default")
      (node (ref "U1") (pin "40") (pinfunction "PC9_40") (pintype "bidirectional"))
    )
    (net (code "81") (name "unconnected-(U1A-PC10-Pad51)") (class "Default")
      (node (ref "U1") (pin "51") (pinfunction "PC10_51") (pintype "bidirectional"))
    )
    (net (code "82") (name "unconnected-(U1A-PC11-Pad52)") (class "Default")
      (node (ref "U1") (pin "52") (pinfunction "PC11_52") (pintype "bidirectional"))
    )
    (net (code "83") (name "unconnected-(U1A-PC12-Pad53)") (class "Default")
      (node (ref "U1") (pin "53") (pinfunction "PC12_53") (pintype "bidirectional"))
    )
    (net (code "84") (name "unconnected-(U1A-PD2-Pad54)") (class "Default")
      (node (ref "U1") (pin "54") (pinfunction "PD2_54") (pintype "bidirectional"))
    )
    (net (code "85") (name "unconnected-(U3-D2{slash}I2C_SDA-Pad20)") (class "Default")
      (node (ref "U3") (pin "20") (pinfunction "D2/I2C_SDA_20") (pintype "bidirectional"))
    )
    (net (code "86") (name "unconnected-(U3-D3-Pad21)") (class "Default")
      (node (ref "U3") (pin "21") (pinfunction "D3_21") (pintype "bidirectional"))
    )
    (net (code "87") (name "unconnected-(U3-D4-Pad22)") (class "Default")
      (node (ref "U3") (pin "22") (pinfunction "D4_22") (pintype "bidirectional"))
    )
    (net (code "88") (name "unconnected-(U3-D5-Pad23)") (class "Default")
      (node (ref "U3") (pin "23") (pinfunction "D5_23") (pintype "bidirectional"))
    )
    (net (code "89") (name "unconnected-(U3-D6-Pad24)") (class "Default")
      (node (ref "U3") (pin "24") (pinfunction "D6_24") (pintype "bidirectional"))
    )
    (net (code "90") (name "unconnected-(U3-D7-Pad25)") (class "Default")
      (node (ref "U3") (pin "25") (pinfunction "D7_25") (pintype "bidirectional"))
    )
    (net (code "91") (name "unconnected-(U3-E{slash}RD-Pad17)") (class "Default")
      (node (ref "U3") (pin "17") (pinfunction "E/RD_17") (pintype "input"))
    )
    (net (code "92") (name "unconnected-(U3-NC-Pad7)") (class "Default")
      (node (ref "U3") (pin "7") (pinfunction "NC_7") (pintype "no_connect"))
    )
    (net (code "93") (name "unconnected-(U3-R{slash}W-Pad16)") (class "Default")
      (node (ref "U3") (pin "16") (pinfunction "R/W_16") (pintype "input"))
    )
    (net (code "94") (name "~{RESET}") (class "Default")
      (node (ref "C2") (pin "1") (pinfunction "1_1") (pintype "passive"))
      (node (ref "J1") (pin "11") (pinfunction "P$11_11") (pintype "bidirectional"))
      (node (ref "J2") (pin "8") (pinfunction "P$8_8") (pintype "bidirectional"))
      (node (ref "J4") (pin "10") (pinfunction "P$10_10") (pintype "bidirectional"))
      (node (ref "U1") (pin "7") (pinfunction "~{RST}_7") (pintype "bidirectional"))
    )
  )
)
